# Schematic.net
KiCad netlist of a schematic drawn in Altium Designer
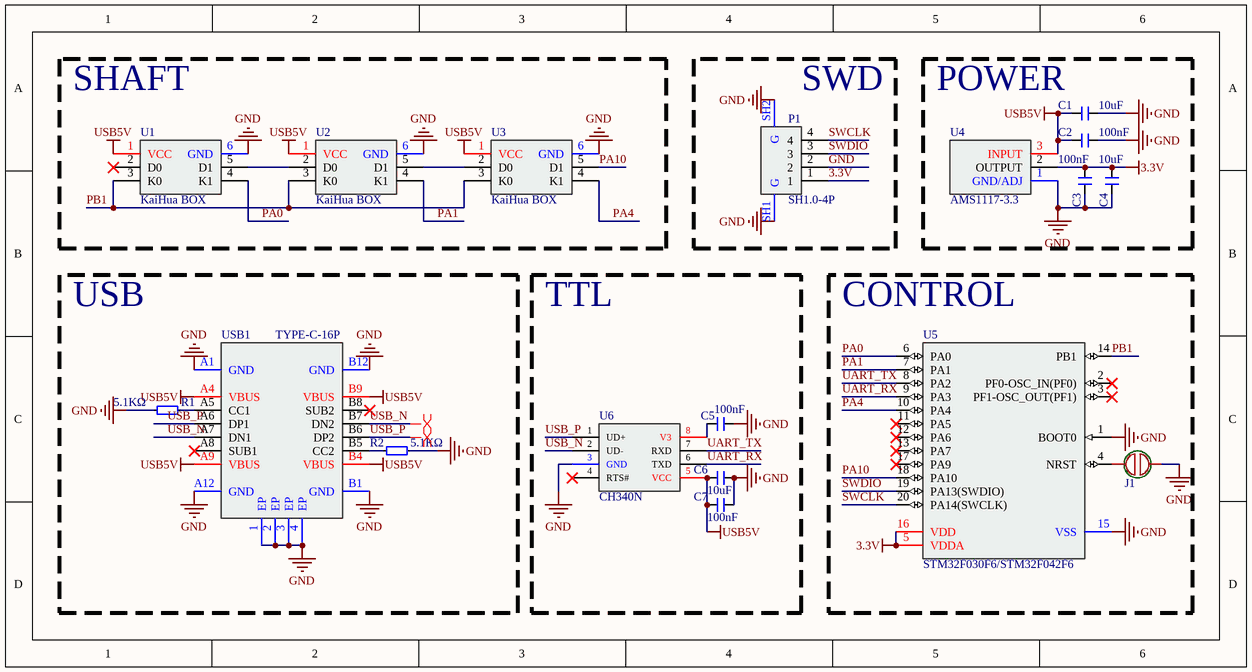
[diagram p0: Schematic.SchDoc]

(export (version "E")
  (design (tool "Eeschema 10.0.6"))
  (components
    (comp (ref "C1")
      (value "10uF")
      (footprint "C0402")
      (description "电容-0402")
      (libsource (lib "IntegratedDevices") (part "C0402"))
    )
    (comp (ref "C2")
      (value "100nF")
      (footprint "C0402")
      (description "电容-0402")
      (libsource (lib "IntegratedDevices") (part "C0402"))
    )
    (comp (ref "C3")
      (value "100nF")
      (footprint "C0402")
      (description "电容-0402")
      (libsource (lib "IntegratedDevices") (part "C0402"))
    )
    (comp (ref "C4")
      (value "10uF")
      (footprint "C0402")
      (description "电容-0402")
      (libsource (lib "IntegratedDevices") (part "C0402"))
    )
    (comp (ref "C5")
      (value "100nF")
      (footprint "C0402")
      (description "电容-0402")
      (libsource (lib "IntegratedDevices") (part "C0402"))
    )
    (comp (ref "C6")
      (value "10uF")
      (footprint "C0402")
      (description "电容-0402")
      (libsource (lib "IntegratedDevices") (part "C0402"))
    )
    (comp (ref "C7")
      (value "100nF")
      (footprint "C0402")
      (description "电容-0402")
      (libsource (lib "IntegratedDevices") (part "C0402"))
    )
    (comp (ref "J1")
      (value "Jumper")
      (footprint "R0402")
      (description "飞线，0Ω电阻")
      (libsource (lib "IntegratedDevices") (part "Jumper"))
    )
    (comp (ref "P1")
      (value "SH1.0-4P")
      (footprint "SH1.0-4P")
      (description "SH1.00mm 4P 卧贴")
      (libsource (lib "IntegratedDevices") (part "SH1.0-4P"))
    )
    (comp (ref "R1")
      (value "5.1KΩ")
      (footprint "R0402")
      (description "电阻-0402")
      (libsource (lib "IntegratedDevices") (part "R0402"))
    )
    (comp (ref "R2")
      (value "5.1KΩ")
      (footprint "R0402")
      (description "电阻-0402")
      (libsource (lib "IntegratedDevices") (part "R0402"))
    )
    (comp (ref "U1")
      (value "KaiHua BOX")
      (footprint "凯华轴座+3528反贴灯")
      (description "凯华轴座+3528反贴灯，缺口在右下")
      (libsource (lib "IntegratedDevices") (part "KaiHua BOX"))
    )
    (comp (ref "U2")
      (value "KaiHua BOX")
      (footprint "凯华轴座+3528反贴灯")
      (description "凯华轴座+3528反贴灯，缺口在右下")
      (libsource (lib "IntegratedDevices") (part "KaiHua BOX"))
    )
    (comp (ref "U3")
      (value "KaiHua BOX")
      (footprint "凯华轴座+3528反贴灯")
      (description "凯华轴座+3528反贴灯，缺口在右下")
      (libsource (lib "IntegratedDevices") (part "KaiHua BOX"))
    )
    (comp (ref "U4")
      (value "AMS1117-3.3")
      (footprint "SOT-89")
      (description "电源IC 降压IC 线性稳压LDO SOT-89封装")
      (libsource (lib "IntegratedDevices") (part "AMS1117-3.3 89"))
    )
    (comp (ref "U5")
      (value "STM32F030F6/STM32F042F6")
      (footprint "TSSOP-20")
      (fields (field (name "PARTNUMBER") "STM32F030F4P6"))
      (libsource (lib "IntegratedDevices") (part "STM32F030F4P6"))
    )
    (comp (ref "U6")
      (value "CH340N")
      (footprint "SOP-8")
      (description "CH340N通讯芯片")
      (libsource (lib "IntegratedDevices") (part "CH340N"))
    )
    (comp (ref "USB1")
      (value "TYPE-C-16P")
      (footprint "TYPE-C-KH Female_LieDown_16P")
      (description "Type-C母座_卧贴_16P")
      (libsource (lib "IntegratedDevices") (part "TYPE-C-KH Female_LieDown_16P"))
    )
  )
  (nets
    (net (code "1") (name "/PA0") (class "Default")
      (node (ref "U1") (pin "4") (pinfunction "K1_4") (pintype "passive"))
      (node (ref "U5") (pin "6") (pinfunction "PA0_6") (pintype "bidirectional"))
    )
    (net (code "2") (name "/PA1") (class "Default")
      (node (ref "U2") (pin "4") (pinfunction "K1_4") (pintype "passive"))
      (node (ref "U5") (pin "7") (pinfunction "PA1_7") (pintype "bidirectional"))
    )
    (net (code "3") (name "/PA4") (class "Default")
      (node (ref "U3") (pin "4") (pinfunction "K1_4") (pintype "passive"))
      (node (ref "U5") (pin "10") (pinfunction "PA4_10") (pintype "bidirectional"))
    )
    (net (code "4") (name "/PA10") (class "Default")
      (node (ref "U3") (pin "5") (pinfunction "D1_5") (pintype "passive"))
      (node (ref "U5") (pin "18") (pinfunction "PA10_18") (pintype "bidirectional"))
    )
    (net (code "5") (name "/PB1") (class "Default")
      (node (ref "U1") (pin "3") (pinfunction "K0_3") (pintype "passive"))
      (node (ref "U2") (pin "3") (pinfunction "K0_3") (pintype "passive"))
      (node (ref "U3") (pin "3") (pinfunction "K0_3") (pintype "passive"))
      (node (ref "U5") (pin "14") (pinfunction "PB1_14") (pintype "bidirectional"))
    )
    (net (code "6") (name "/SWCLK") (class "Default")
      (node (ref "P1") (pin "4") (pinfunction "4_4") (pintype "passive"))
      (node (ref "U5") (pin "20") (pinfunction "PA14(SWCLK)_20") (pintype "bidirectional"))
    )
    (net (code "7") (name "/SWDIO") (class "Default")
      (node (ref "P1") (pin "3") (pinfunction "3_3") (pintype "passive"))
      (node (ref "U5") (pin "19") (pinfunction "PA13(SWDIO)_19") (pintype "bidirectional"))
    )
    (net (code "8") (name "/UART_RX") (class "Default")
      (node (ref "U5") (pin "9") (pinfunction "PA3_9") (pintype "bidirectional"))
      (node (ref "U6") (pin "6") (pinfunction "TXD_6") (pintype "passive"))
    )
    (net (code "9") (name "/UART_TX") (class "Default")
      (node (ref "U5") (pin "8") (pinfunction "PA2_8") (pintype "bidirectional"))
      (node (ref "U6") (pin "7") (pinfunction "RXD_7") (pintype "passive"))
    )
    (net (code "10") (name "/USB_N") (class "Default")
      (node (ref "U6") (pin "2") (pinfunction "UD-_2") (pintype "passive"))
      (node (ref "USB1") (pin "A7") (pinfunction "DN1_A7") (pintype "passive"))
      (node (ref "USB1") (pin "B7") (pinfunction "DN2_B7") (pintype "passive"))
    )
    (net (code "11") (name "/USB_P") (class "Default")
      (node (ref "U6") (pin "1") (pinfunction "UD+_1") (pintype "passive"))
      (node (ref "USB1") (pin "A6") (pinfunction "DP1_A6") (pintype "passive"))
      (node (ref "USB1") (pin "B6") (pinfunction "DP2_B6") (pintype "passive"))
    )
    (net (code "12") (name "3.3V") (class "Default")
      (node (ref "C3") (pin "2") (pinfunction "2_2") (pintype "passive"))
      (node (ref "C4") (pin "2") (pinfunction "2_2") (pintype "passive"))
      (node (ref "P1") (pin "1") (pinfunction "1_1") (pintype "passive"))
      (node (ref "U4") (pin "2") (pinfunction "OUTPUT_2") (pintype "passive"))
      (node (ref "U5") (pin "16") (pinfunction "VDD_16") (pintype "power_in"))
      (node (ref "U5") (pin "5") (pinfunction "VDDA_5") (pintype "power_in"))
    )
    (net (code "13") (name "GND") (class "Default")
      (node (ref "C1") (pin "2") (pinfunction "2_2") (pintype "passive"))
      (node (ref "C2") (pin "2") (pinfunction "2_2") (pintype "passive"))
      (node (ref "C3") (pin "1") (pinfunction "1_1") (pintype "passive"))
      (node (ref "C4") (pin "1") (pinfunction "1_1") (pintype "passive"))
      (node (ref "C5") (pin "2") (pinfunction "2_2") (pintype "passive"))
      (node (ref "C6") (pin "2") (pinfunction "2_2") (pintype "passive"))
      (node (ref "C7") (pin "2") (pinfunction "2_2") (pintype "passive"))
      (node (ref "J1") (pin "2") (pinfunction "2_2") (pintype "passive"))
      (node (ref "P1") (pin "2") (pinfunction "2_2") (pintype "passive"))
      (node (ref "P1") (pin "SH1") (pinfunction "G_SH1") (pintype "passive"))
      (node (ref "P1") (pin "SH2") (pinfunction "G_SH2") (pintype "passive"))
      (node (ref "R1") (pin "1") (pinfunction "1_1") (pintype "passive"))
      (node (ref "R2") (pin "2") (pinfunction "2_2") (pintype "passive"))
      (node (ref "U1") (pin "6") (pinfunction "GND_6") (pintype "passive"))
      (node (ref "U2") (pin "6") (pinfunction "GND_6") (pintype "passive"))
      (node (ref "U3") (pin "6") (pinfunction "GND_6") (pintype "passive"))
      (node (ref "U4") (pin "1") (pinfunction "GND/ADJ_1") (pintype "passive"))
      (node (ref "U5") (pin "1") (pinfunction "BOOT0_1") (pintype "input"))
      (node (ref "U5") (pin "15") (pinfunction "VSS_15") (pintype "power_in"))
      (node (ref "U6") (pin "3") (pinfunction "GND_3") (pintype "passive"))
      (node (ref "USB1") (pin "1") (pinfunction "EP_1") (pintype "passive"))
      (node (ref "USB1") (pin "2") (pinfunction "EP_2") (pintype "passive"))
      (node (ref "USB1") (pin "3") (pinfunction "EP_3") (pintype "passive"))
      (node (ref "USB1") (pin "4") (pinfunction "EP_4") (pintype "passive"))
      (node (ref "USB1") (pin "A1") (pinfunction "GND_A1") (pintype "passive"))
      (node (ref "USB1") (pin "A12") (pinfunction "GND_A12") (pintype "passive"))
      (node (ref "USB1") (pin "B1") (pinfunction "GND_B1") (pintype "passive"))
      (node (ref "USB1") (pin "B12") (pinfunction "GND_B12") (pintype "passive"))
    )
    (net (code "14") (name "Net-(U1-D1)") (class "Default")
      (node (ref "U1") (pin "5") (pinfunction "D1_5") (pintype "passive"))
      (node (ref "U2") (pin "2") (pinfunction "D0_2") (pintype "passive"))
    )
    (net (code "15") (name "Net-(U2-D1)") (class "Default")
      (node (ref "U2") (pin "5") (pinfunction "D1_5") (pintype "passive"))
      (node (ref "U3") (pin "2") (pinfunction "D0_2") (pintype "passive"))
    )
    (net (code "16") (name "Net-(U5-NRST)") (class "Default")
      (node (ref "J1") (pin "1") (pinfunction "1_1") (pintype "passive"))
      (node (ref "U5") (pin "4") (pinfunction "NRST_4") (pintype "bidirectional"))
    )
    (net (code "17") (name "Net-(U6-V3)") (class "Default")
      (node (ref "C5") (pin "1") (pinfunction "1_1") (pintype "passive"))
      (node (ref "U6") (pin "8") (pinfunction "V3_8") (pintype "passive"))
    )
    (net (code "18") (name "Net-(USB1-CC1)") (class "Default")
      (node (ref "R1") (pin "2") (pinfunction "2_2") (pintype "passive"))
      (node (ref "USB1") (pin "A5") (pinfunction "CC1_A5") (pintype "passive"))
    )
    (net (code "19") (name "Net-(USB1-CC2)") (class "Default")
      (node (ref "R2") (pin "1") (pinfunction "1_1") (pintype "passive"))
      (node (ref "USB1") (pin "B5") (pinfunction "CC2_B5") (pintype "passive"))
    )
    (net (code "20") (name "USB5V") (class "Default")
      (node (ref "C1") (pin "1") (pinfunction "1_1") (pintype "passive"))
      (node (ref "C2") (pin "1") (pinfunction "1_1") (pintype "passive"))
      (node (ref "C6") (pin "1") (pinfunction "1_1") (pintype "passive"))
      (node (ref "C7") (pin "1") (pinfunction "1_1") (pintype "passive"))
      (node (ref "U1") (pin "1") (pinfunction "VCC_1") (pintype "passive"))
      (node (ref "U2") (pin "1") (pinfunction "VCC_1") (pintype "passive"))
      (node (ref "U3") (pin "1") (pinfunction "VCC_1") (pintype "passive"))
      (node (ref "U4") (pin "3") (pinfunction "INPUT_3") (pintype "passive"))
      (node (ref "U6") (pin "5") (pinfunction "VCC_5") (pintype "passive"))
      (node (ref "USB1") (pin "A4") (pinfunction "VBUS_A4") (pintype "passive"))
      (node (ref "USB1") (pin "A9") (pinfunction "VBUS_A9") (pintype "passive"))
      (node (ref "USB1") (pin "B4") (pinfunction "VBUS_B4") (pintype "passive"))
      (node (ref "USB1") (pin "B9") (pinfunction "VBUS_B9") (pintype "passive"))
    )
    (net (code "21") (name "unconnected-(U1-D0-Pad2)") (class "Default")
      (node (ref "U1") (pin "2") (pinfunction "D0_2") (pintype "passive+no_connect"))
    )
    (net (code "22") (name "unconnected-(U5-PA5-Pad11)") (class "Default")
      (node (ref "U5") (pin "11") (pinfunction "PA5_11") (pintype "bidirectional+no_connect"))
    )
    (net (code "23") (name "unconnected-(U5-PA6-Pad12)") (class "Default")
      (node (ref "U5") (pin "12") (pinfunction "PA6_12") (pintype "bidirectional+no_connect"))
    )
    (net (code "24") (name "unconnected-(U5-PA7-Pad13)") (class "Default")
      (node (ref "U5") (pin "13") (pinfunction "PA7_13") (pintype "bidirectional+no_connect"))
    )
    (net (code "25") (name "unconnected-(U5-PA9-Pad17)") (class "Default")
      (node (ref "U5") (pin "17") (pinfunction "PA9_17") (pintype "bidirectional+no_connect"))
    )
    (net (code "26") (name "unconnected-(U5-PF0-OSC_IN(PF0)-Pad2)") (class "Default")
      (node (ref "U5") (pin "2") (pinfunction "PF0-OSC_IN(PF0)_2") (pintype "bidirectional+no_connect"))
    )
    (net (code "27") (name "unconnected-(U5-PF1-OSC_OUT(PF1)-Pad3)") (class "Default")
      (node (ref "U5") (pin "3") (pinfunction "PF1-OSC_OUT(PF1)_3") (pintype "bidirectional+no_connect"))
    )
    (net (code "28") (name "unconnected-(U6-RTS#-Pad4)") (class "Default")
      (node (ref "U6") (pin "4") (pinfunction "RTS#_4") (pintype "passive+no_connect"))
    )
    (net (code "29") (name "unconnected-(USB1-SUB1-PadA8)") (class "Default")
      (node (ref "USB1") (pin "A8") (pinfunction "SUB1_A8") (pintype "passive+no_connect"))
    )
    (net (code "30") (name "unconnected-(USB1-SUB2-PadB8)") (class "Default")
      (node (ref "USB1") (pin "B8") (pinfunction "SUB2_B8") (pintype "passive+no_connect"))
    )
  )
)
